# ADC.net
KiCad netlist of a schematic drawn in Altium Designer
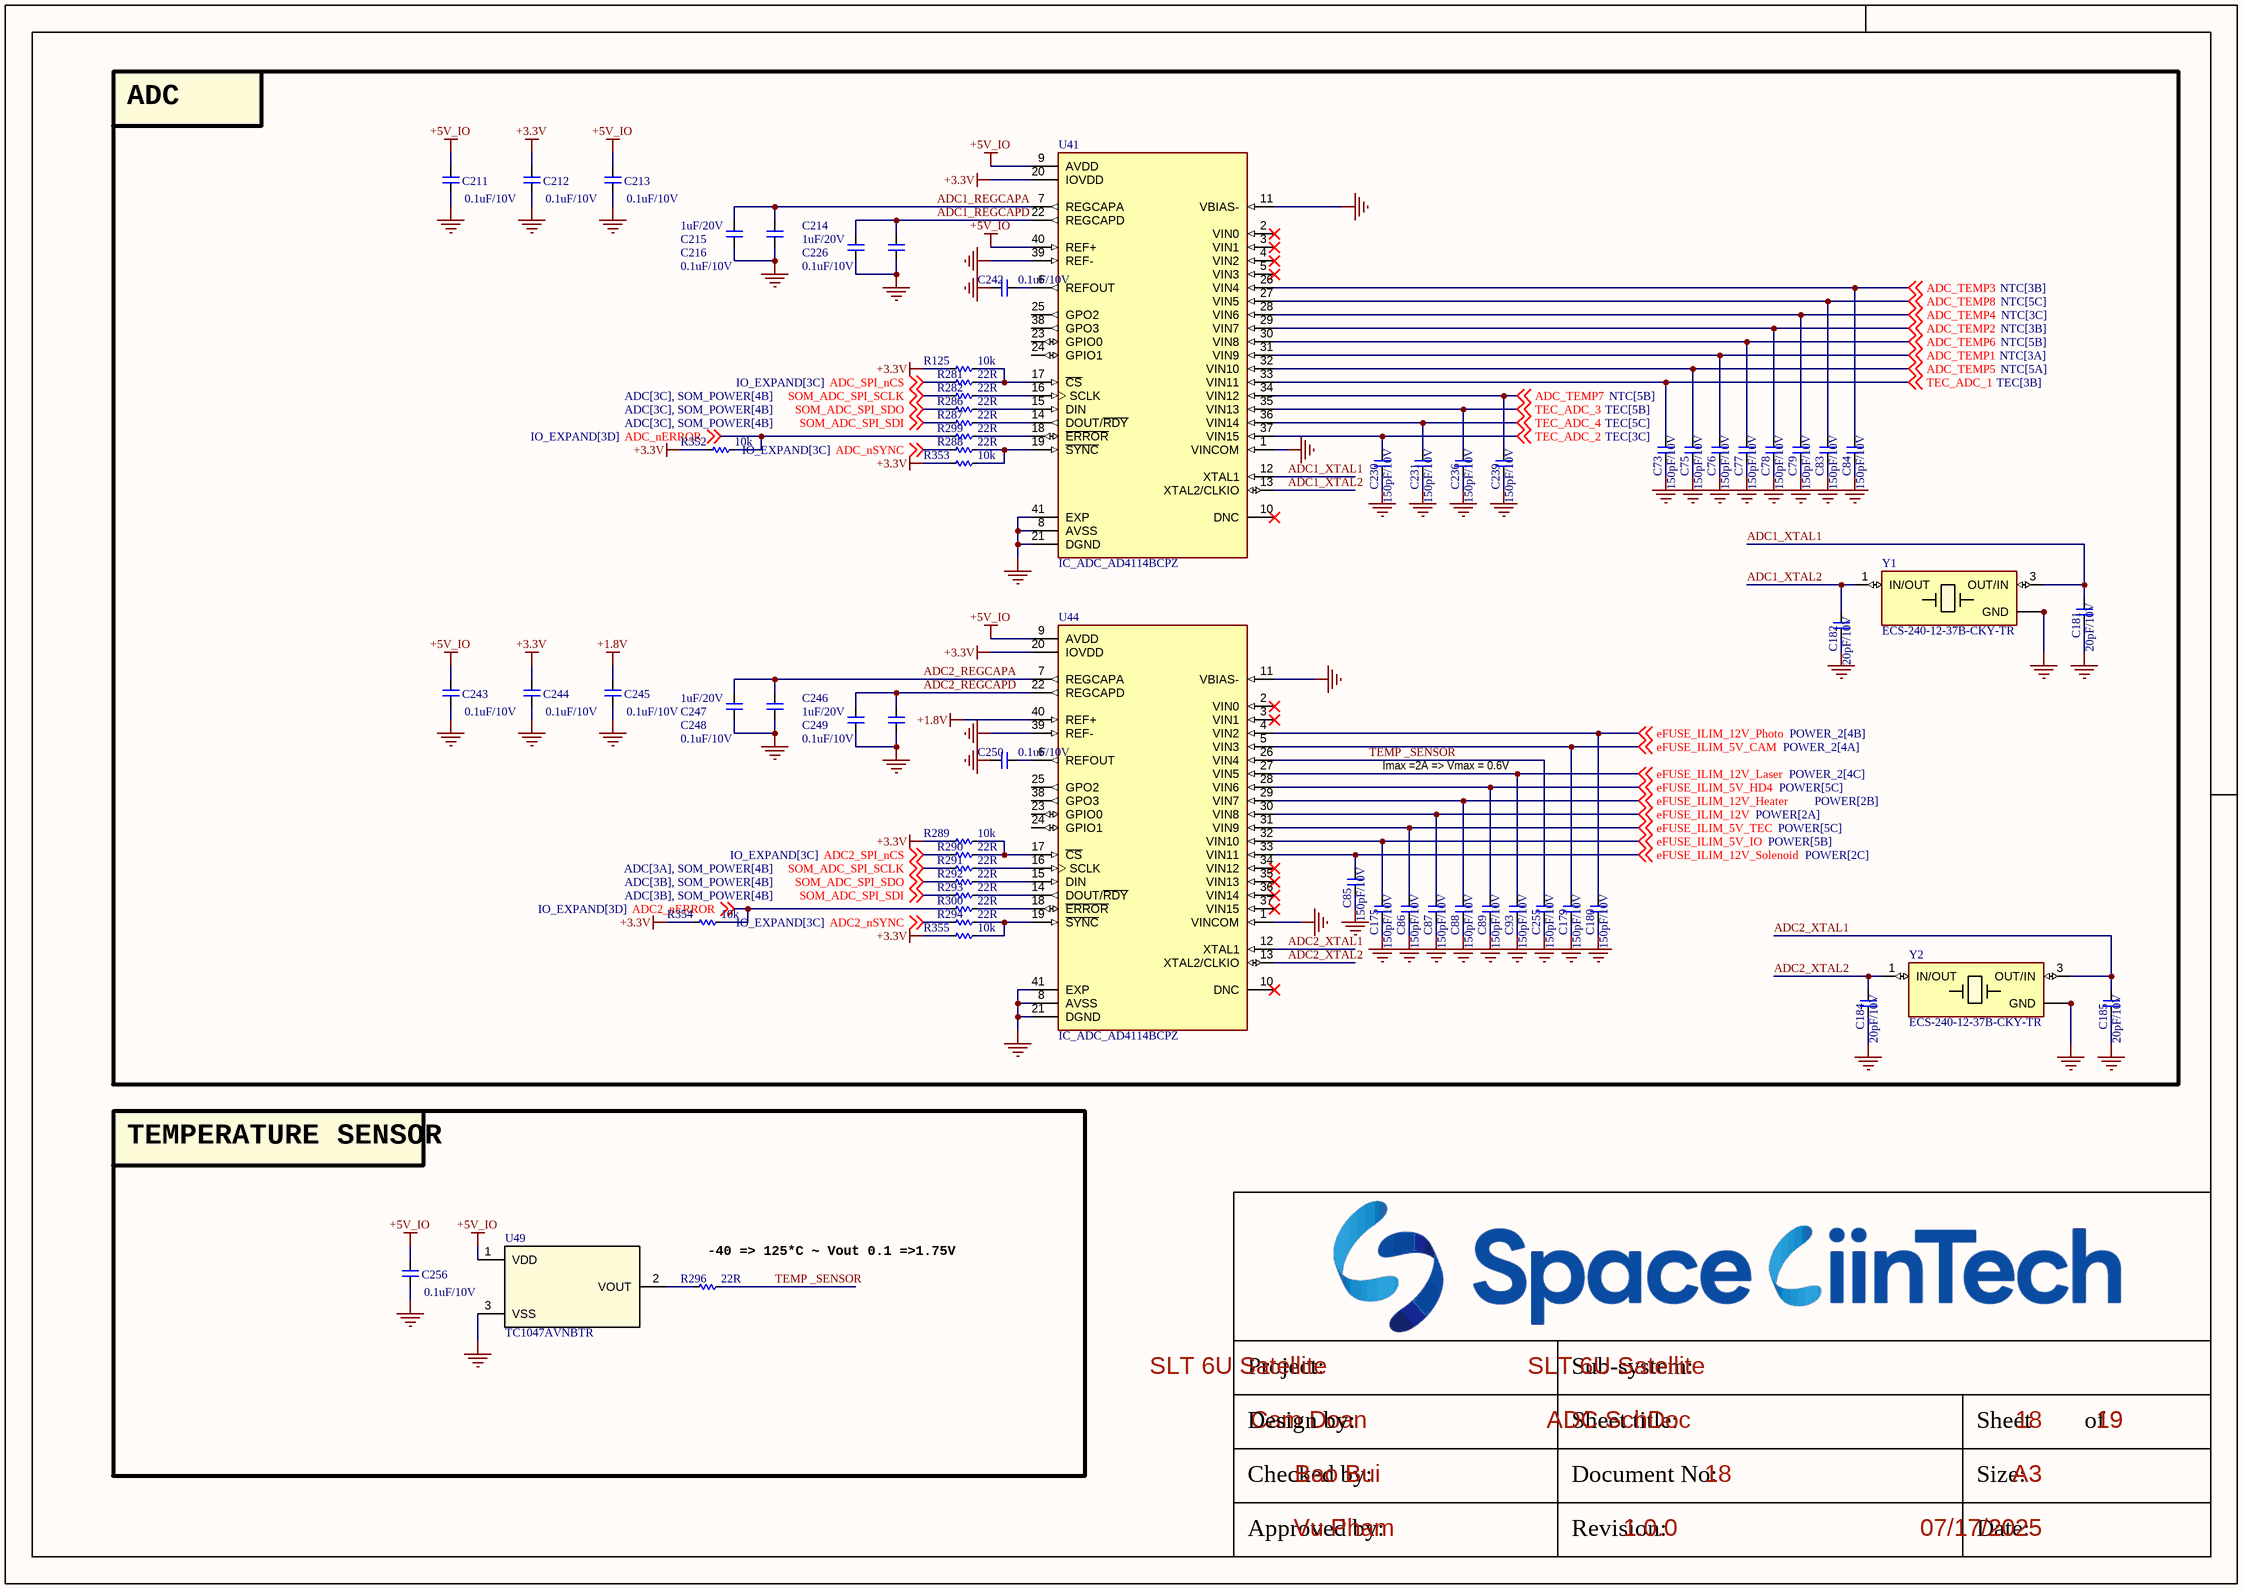
[diagram p0: ADC.SchDoc]

(export (version "E")
  (design (tool "Eeschema 10.0.6"))
  (components
    (comp (ref "C73")
      (value "150pF/10V")
      (footprint "CAP_C_1005X60")
      (description "CAP CHIP")
      (libsource (lib "LABLIB") (part "_CAP_C_2"))
    )
    (comp (ref "C75")
      (value "150pF/10V")
      (footprint "CAP_C_1005X60")
      (description "CAP CHIP")
      (libsource (lib "LABLIB") (part "_CAP_C_2"))
    )
    (comp (ref "C76")
      (value "150pF/10V")
      (footprint "CAP_C_1005X60")
      (description "CAP CHIP")
      (libsource (lib "LABLIB") (part "_CAP_C_2"))
    )
    (comp (ref "C77")
      (value "150pF/10V")
      (footprint "CAP_C_1005X60")
      (description "CAP CHIP")
      (libsource (lib "LABLIB") (part "_CAP_C_2"))
    )
    (comp (ref "C78")
      (value "150pF/10V")
      (footprint "CAP_C_1005X60")
      (description "CAP CHIP")
      (libsource (lib "LABLIB") (part "_CAP_C_2"))
    )
    (comp (ref "C79")
      (value "150pF/10V")
      (footprint "CAP_C_1005X60")
      (description "CAP CHIP")
      (libsource (lib "LABLIB") (part "_CAP_C_2"))
    )
    (comp (ref "C83")
      (value "150pF/10V")
      (footprint "CAP_C_1005X60")
      (description "CAP CHIP")
      (libsource (lib "LABLIB") (part "_CAP_C_2"))
    )
    (comp (ref "C84")
      (value "150pF/10V")
      (footprint "CAP_C_1005X60")
      (description "CAP CHIP")
      (libsource (lib "LABLIB") (part "_CAP_C_2"))
    )
    (comp (ref "C85")
      (value "150pF/10V")
      (footprint "CAP_C_1005X60")
      (description "CAP CHIP")
      (libsource (lib "LABLIB") (part "_CAP_C_2"))
    )
    (comp (ref "C86")
      (value "150pF/10V")
      (footprint "CAP_C_1005X60")
      (description "CAP CHIP")
      (libsource (lib "LABLIB") (part "_CAP_C_2"))
    )
    (comp (ref "C87")
      (value "150pF/10V")
      (footprint "CAP_C_1005X60")
      (description "CAP CHIP")
      (libsource (lib "LABLIB") (part "_CAP_C_2"))
    )
    (comp (ref "C88")
      (value "150pF/10V")
      (footprint "CAP_C_1005X60")
      (description "CAP CHIP")
      (libsource (lib "LABLIB") (part "_CAP_C_2"))
    )
    (comp (ref "C89")
      (value "150pF/10V")
      (footprint "CAP_C_1005X60")
      (description "CAP CHIP")
      (libsource (lib "LABLIB") (part "_CAP_C_2"))
    )
    (comp (ref "C93")
      (value "150pF/10V")
      (footprint "CAP_C_1005X60")
      (description "CAP CHIP")
      (libsource (lib "LABLIB") (part "_CAP_C_2"))
    )
    (comp (ref "C175")
      (value "150pF/10V")
      (footprint "CAP_C_1005X60")
      (description "CAP CHIP")
      (libsource (lib "LABLIB") (part "_CAP_C_2"))
    )
    (comp (ref "C179")
      (value "150pF/10V")
      (footprint "CAP_C_1005X60")
      (description "CAP CHIP")
      (libsource (lib "LABLIB") (part "_CAP_C_2"))
    )
    (comp (ref "C180")
      (value "150pF/10V")
      (footprint "CAP_C_1005X60")
      (description "CAP CHIP")
      (libsource (lib "LABLIB") (part "_CAP_C_2"))
    )
    (comp (ref "C181")
      (value "20pF/10V")
      (footprint "CAP_C_1005X60")
      (description "CAP CHIP")
      (libsource (lib "LABLIB") (part "_CAP_C_2"))
    )
    (comp (ref "C182")
      (value "20pF/10V")
      (footprint "CAP_C_1005X60")
      (description "CAP CHIP")
      (libsource (lib "LABLIB") (part "_CAP_C_2"))
    )
    (comp (ref "C184")
      (value "20pF/10V")
      (footprint "CAP_C_1005X60")
      (description "CAP CHIP")
      (libsource (lib "LABLIB") (part "_CAP_C_2"))
    )
    (comp (ref "C185")
      (value "20pF/10V")
      (footprint "CAP_C_1005X60")
      (description "CAP CHIP")
      (libsource (lib "LABLIB") (part "_CAP_C_2"))
    )
    (comp (ref "C211")
      (value "0.1uF/10V")
      (footprint "CAP_C_1005X60")
      (description "CAP CHIP")
      (libsource (lib "LABLIB") (part "_CAP_C_2"))
    )
    (comp (ref "C212")
      (value "0.1uF/10V")
      (footprint "CAP_C_1005X60")
      (description "CAP CHIP")
      (libsource (lib "LABLIB") (part "_CAP_C_2"))
    )
    (comp (ref "C213")
      (value "0.1uF/10V")
      (footprint "CAP_C_1005X60")
      (description "CAP CHIP")
      (libsource (lib "LABLIB") (part "_CAP_C_2"))
    )
    (comp (ref "C214")
      (value "1uF/20V")
      (footprint "CAP_C_1005X60")
      (description "CAP CHIP")
      (libsource (lib "LABLIB") (part "_CAP_C_2"))
    )
    (comp (ref "C215")
      (value "1uF/20V")
      (footprint "CAP_C_1005X60")
      (description "CAP CHIP")
      (libsource (lib "LABLIB") (part "_CAP_C_2"))
    )
    (comp (ref "C216")
      (value "0.1uF/10V")
      (footprint "CAP_C_1005X60")
      (description "CAP CHIP")
      (libsource (lib "LABLIB") (part "_CAP_C_2"))
    )
    (comp (ref "C226")
      (value "0.1uF/10V")
      (footprint "CAP_C_1005X60")
      (description "CAP CHIP")
      (libsource (lib "LABLIB") (part "_CAP_C_2"))
    )
    (comp (ref "C230")
      (value "150pF/10V")
      (footprint "CAP_C_1005X60")
      (description "CAP CHIP")
      (libsource (lib "LABLIB") (part "_CAP_C_2"))
    )
    (comp (ref "C231")
      (value "150pF/10V")
      (footprint "CAP_C_1005X60")
      (description "CAP CHIP")
      (libsource (lib "LABLIB") (part "_CAP_C_2"))
    )
    (comp (ref "C236")
      (value "150pF/10V")
      (footprint "CAP_C_1005X60")
      (description "CAP CHIP")
      (libsource (lib "LABLIB") (part "_CAP_C_2"))
    )
    (comp (ref "C239")
      (value "150pF/10V")
      (footprint "CAP_C_1005X60")
      (description "CAP CHIP")
      (libsource (lib "LABLIB") (part "_CAP_C_2"))
    )
    (comp (ref "C242")
      (value "0.1uF/10V")
      (footprint "CAP_C_1005X60")
      (description "CAP CHIP")
      (libsource (lib "LABLIB") (part "_CAP_C_2"))
    )
    (comp (ref "C243")
      (value "0.1uF/10V")
      (footprint "CAP_C_1005X60")
      (description "CAP CHIP")
      (libsource (lib "LABLIB") (part "_CAP_C_2"))
    )
    (comp (ref "C244")
      (value "0.1uF/10V")
      (footprint "CAP_C_1005X60")
      (description "CAP CHIP")
      (libsource (lib "LABLIB") (part "_CAP_C_2"))
    )
    (comp (ref "C245")
      (value "0.1uF/10V")
      (footprint "CAP_C_1005X60")
      (description "CAP CHIP")
      (libsource (lib "LABLIB") (part "_CAP_C_2"))
    )
    (comp (ref "C246")
      (value "1uF/20V")
      (footprint "CAP_C_1005X60")
      (description "CAP CHIP")
      (libsource (lib "LABLIB") (part "_CAP_C_2"))
    )
    (comp (ref "C247")
      (value "1uF/20V")
      (footprint "CAP_C_1005X60")
      (description "CAP CHIP")
      (libsource (lib "LABLIB") (part "_CAP_C_2"))
    )
    (comp (ref "C248")
      (value "0.1uF/10V")
      (footprint "CAP_C_1005X60")
      (description "CAP CHIP")
      (libsource (lib "LABLIB") (part "_CAP_C_2"))
    )
    (comp (ref "C249")
      (value "0.1uF/10V")
      (footprint "CAP_C_1005X60")
      (description "CAP CHIP")
      (libsource (lib "LABLIB") (part "_CAP_C_2"))
    )
    (comp (ref "C250")
      (value "0.1uF/10V")
      (footprint "CAP_C_1005X60")
      (description "CAP CHIP")
      (libsource (lib "LABLIB") (part "_CAP_C_2"))
    )
    (comp (ref "C255")
      (value "150pF/10V")
      (footprint "CAP_C_1005X60")
      (description "CAP CHIP")
      (libsource (lib "LABLIB") (part "_CAP_C_2"))
    )
    (comp (ref "C256")
      (value "0.1uF/10V")
      (footprint "CAP_C_1005X60")
      (description "CAP CHIP")
      (libsource (lib "LABLIB") (part "_CAP_C_2"))
    )
    (comp (ref "R125")
      (value "10k")
      (footprint "RES_C_1005X40")
      (description "RES")
      (libsource (lib "LABLIB") (part "_RES_B_2"))
    )
    (comp (ref "R281")
      (value "22R")
      (footprint "RES_C_1005X40")
      (description "RES")
      (libsource (lib "LABLIB") (part "_RES_B_2"))
    )
    (comp (ref "R282")
      (value "22R")
      (footprint "RES_C_1005X40")
      (description "RES")
      (libsource (lib "LABLIB") (part "_RES_B_2"))
    )
    (comp (ref "R286")
      (value "22R")
      (footprint "RES_C_1005X40")
      (description "RES")
      (libsource (lib "LABLIB") (part "_RES_B_2"))
    )
    (comp (ref "R287")
      (value "22R")
      (footprint "RES_C_1005X40")
      (description "RES")
      (libsource (lib "LABLIB") (part "_RES_B_2"))
    )
    (comp (ref "R288")
      (value "22R")
      (footprint "RES_C_1005X40")
      (description "RES")
      (libsource (lib "LABLIB") (part "_RES_B_2"))
    )
    (comp (ref "R289")
      (value "10k")
      (footprint "RES_C_1005X40")
      (description "RES")
      (libsource (lib "LABLIB") (part "_RES_B_2"))
    )
    (comp (ref "R290")
      (value "22R")
      (footprint "RES_C_1005X40")
      (description "RES")
      (libsource (lib "LABLIB") (part "_RES_B_2"))
    )
    (comp (ref "R291")
      (value "22R")
      (footprint "RES_C_1005X40")
      (description "RES")
      (libsource (lib "LABLIB") (part "_RES_B_2"))
    )
    (comp (ref "R292")
      (value "22R")
      (footprint "RES_C_1005X40")
      (description "RES")
      (libsource (lib "LABLIB") (part "_RES_B_2"))
    )
    (comp (ref "R293")
      (value "22R")
      (footprint "RES_C_1005X40")
      (description "RES")
      (libsource (lib "LABLIB") (part "_RES_B_2"))
    )
    (comp (ref "R294")
      (value "22R")
      (footprint "RES_C_1005X40")
      (description "RES")
      (libsource (lib "LABLIB") (part "_RES_B_2"))
    )
    (comp (ref "R296")
      (value "22R")
      (footprint "RES_C_1005X40")
      (description "RES")
      (libsource (lib "LABLIB") (part "_RES_B_2"))
    )
    (comp (ref "R299")
      (value "22R")
      (footprint "RES_C_1005X40")
      (description "RES")
      (libsource (lib "LABLIB") (part "_RES_B_2"))
    )
    (comp (ref "R300")
      (value "22R")
      (footprint "RES_C_1005X40")
      (description "RES")
      (libsource (lib "LABLIB") (part "_RES_B_2"))
    )
    (comp (ref "R352")
      (value "10k")
      (footprint "RES_C_1005X40")
      (description "RES")
      (libsource (lib "LABLIB") (part "_RES_B_2"))
    )
    (comp (ref "R353")
      (value "10k")
      (footprint "RES_C_1005X40")
      (description "RES")
      (libsource (lib "LABLIB") (part "_RES_B_2"))
    )
    (comp (ref "R354")
      (value "10k")
      (footprint "RES_C_1005X40")
      (description "RES")
      (libsource (lib "LABLIB") (part "_RES_B_2"))
    )
    (comp (ref "R355")
      (value "10k")
      (footprint "RES_C_1005X40")
      (description "RES")
      (libsource (lib "LABLIB") (part "_RES_B_2"))
    )
    (comp (ref "U41")
      (value "IC_ADC_AD4114BCPZ")
      (footprint "QFN50P600X600X100-41N")
      (description "Single Supply, Multichannel, 31.25 kSPS, 24-Bit, Sigma-Delta ADC with Â±10 V Inputs")
      (fields (field (name "MP") "AD4114BCPZ") (field (name "MF") "Analog Devices"))
      (libsource (lib "LABLIB") (part "IC_ADC_AD4114BCPZ"))
    )
    (comp (ref "U44")
      (value "IC_ADC_AD4114BCPZ")
      (footprint "QFN50P600X600X100-41N")
      (description "Single Supply, Multichannel, 31.25 kSPS, 24-Bit, Sigma-Delta ADC with Â±10 V Inputs")
      (fields (field (name "MP") "AD4114BCPZ") (field (name "MF") "Analog Devices"))
      (libsource (lib "LABLIB") (part "IC_ADC_AD4114BCPZ"))
    )
    (comp (ref "U49")
      (value "TC1047AVNBTR")
      (footprint "SOT95P240X120-3N")
      (description "Temperature Sensor Analog, Local -40°C ~ 125°C 10mV/°C SOT-23-3")
      (libsource (lib "LABLIB") (part "IC_SENSOR_TC1047AVNBTR"))
    )
    (comp (ref "Y1")
      (value "ECS-240-12-37B-CKY-TR")
      (footprint "XTAL_ECS-240-12-37B-CKY-TR")
      (libsource (lib "ECS-240-12-37B-CKY-TR") (part "ECS-240-12-37B-CKY-TR"))
    )
    (comp (ref "Y2")
      (value "ECS-240-12-37B-CKY-TR")
      (footprint "XTAL_ECS-240-12-37B-CKY-TR")
      (libsource (lib "ECS-240-12-37B-CKY-TR") (part "ECS-240-12-37B-CKY-TR"))
    )
  )
  (nets
    (net (code "1") (name "+1.8V") (class "Default")
      (node (ref "C245") (pin "2") (pinfunction "2_2") (pintype "passive"))
      (node (ref "U44") (pin "40") (pinfunction "REF+_40") (pintype "input"))
    )
    (net (code "2") (name "+3.3V") (class "Default")
      (node (ref "C212") (pin "2") (pinfunction "2_2") (pintype "passive"))
      (node (ref "C244") (pin "2") (pinfunction "2_2") (pintype "passive"))
      (node (ref "R125") (pin "2") (pinfunction "2_2") (pintype "passive"))
      (node (ref "R289") (pin "2") (pinfunction "2_2") (pintype "passive"))
      (node (ref "R352") (pin "2") (pinfunction "2_2") (pintype "passive"))
      (node (ref "R353") (pin "2") (pinfunction "2_2") (pintype "passive"))
      (node (ref "R354") (pin "2") (pinfunction "2_2") (pintype "passive"))
      (node (ref "R355") (pin "2") (pinfunction "2_2") (pintype "passive"))
      (node (ref "U41") (pin "20") (pinfunction "IOVDD_20") (pintype "power_in"))
      (node (ref "U44") (pin "20") (pinfunction "IOVDD_20") (pintype "power_in"))
    )
    (net (code "3") (name "+5V_IO") (class "Default")
      (node (ref "C211") (pin "2") (pinfunction "2_2") (pintype "passive"))
      (node (ref "C213") (pin "2") (pinfunction "2_2") (pintype "passive"))
      (node (ref "C243") (pin "2") (pinfunction "2_2") (pintype "passive"))
      (node (ref "C256") (pin "2") (pinfunction "2_2") (pintype "passive"))
      (node (ref "U41") (pin "40") (pinfunction "REF+_40") (pintype "input"))
      (node (ref "U41") (pin "9") (pinfunction "AVDD_9") (pintype "power_in"))
      (node (ref "U44") (pin "9") (pinfunction "AVDD_9") (pintype "power_in"))
      (node (ref "U49") (pin "1") (pinfunction "VDD_1") (pintype "passive"))
    )
    (net (code "4") (name "/ADC1_REGCAPA") (class "Default")
      (node (ref "C215") (pin "2") (pinfunction "2_2") (pintype "passive"))
      (node (ref "C216") (pin "2") (pinfunction "2_2") (pintype "passive"))
      (node (ref "U41") (pin "7") (pinfunction "REGCAPA_7") (pintype "output"))
    )
    (net (code "5") (name "/ADC1_REGCAPD") (class "Default")
      (node (ref "C214") (pin "2") (pinfunction "2_2") (pintype "passive"))
      (node (ref "C226") (pin "2") (pinfunction "2_2") (pintype "passive"))
      (node (ref "U41") (pin "22") (pinfunction "REGCAPD_22") (pintype "output"))
    )
    (net (code "6") (name "/ADC1_XTAL1") (class "Default")
      (node (ref "C181") (pin "2") (pinfunction "2_2") (pintype "passive"))
      (node (ref "U41") (pin "12") (pinfunction "XTAL1_12") (pintype "input"))
      (node (ref "Y1") (pin "3") (pinfunction "OUT/IN_3") (pintype "bidirectional"))
    )
    (net (code "7") (name "/ADC1_XTAL2") (class "Default")
      (node (ref "C182") (pin "2") (pinfunction "2_2") (pintype "passive"))
      (node (ref "U41") (pin "13") (pinfunction "XTAL2/CLKIO_13") (pintype "bidirectional"))
      (node (ref "Y1") (pin "1") (pinfunction "IN/OUT_1") (pintype "bidirectional"))
    )
    (net (code "8") (name "/ADC2_REGCAPA") (class "Default")
      (node (ref "C247") (pin "2") (pinfunction "2_2") (pintype "passive"))
      (node (ref "C248") (pin "2") (pinfunction "2_2") (pintype "passive"))
      (node (ref "U44") (pin "7") (pinfunction "REGCAPA_7") (pintype "output"))
    )
    (net (code "9") (name "/ADC2_REGCAPD") (class "Default")
      (node (ref "C246") (pin "2") (pinfunction "2_2") (pintype "passive"))
      (node (ref "C249") (pin "2") (pinfunction "2_2") (pintype "passive"))
      (node (ref "U44") (pin "22") (pinfunction "REGCAPD_22") (pintype "output"))
    )
    (net (code "10") (name "/ADC2_XTAL1") (class "Default")
      (node (ref "C185") (pin "2") (pinfunction "2_2") (pintype "passive"))
      (node (ref "U44") (pin "12") (pinfunction "XTAL1_12") (pintype "input"))
      (node (ref "Y2") (pin "3") (pinfunction "OUT/IN_3") (pintype "bidirectional"))
    )
    (net (code "11") (name "/ADC2_XTAL2") (class "Default")
      (node (ref "C184") (pin "2") (pinfunction "2_2") (pintype "passive"))
      (node (ref "U44") (pin "13") (pinfunction "XTAL2/CLKIO_13") (pintype "bidirectional"))
      (node (ref "Y2") (pin "1") (pinfunction "IN/OUT_1") (pintype "bidirectional"))
    )
    (net (code "12") (name "/TEMP _SENSOR") (class "Default")
      (node (ref "C255") (pin "2") (pinfunction "2_2") (pintype "passive"))
      (node (ref "R296") (pin "2") (pinfunction "2_2") (pintype "passive"))
      (node (ref "U44") (pin "26") (pinfunction "VIN4_26") (pintype "input"))
    )
    (net (code "13") (name "ADC2_SPI_nCS") (class "Default")
      (node (ref "R290") (pin "1") (pinfunction "1_1") (pintype "passive"))
    )
    (net (code "14") (name "ADC2_nERROR") (class "Default")
      (node (ref "R300") (pin "1") (pinfunction "1_1") (pintype "passive"))
      (node (ref "R354") (pin "1") (pinfunction "1_1") (pintype "passive"))
    )
    (net (code "15") (name "ADC2_nSYNC") (class "Default")
      (node (ref "R294") (pin "1") (pinfunction "1_1") (pintype "passive"))
    )
    (net (code "16") (name "ADC_SPI_nCS") (class "Default")
      (node (ref "R281") (pin "1") (pinfunction "1_1") (pintype "passive"))
    )
    (net (code "17") (name "ADC_TEMP1") (class "Default")
      (node (ref "C76") (pin "2") (pinfunction "2_2") (pintype "passive"))
      (node (ref "U41") (pin "31") (pinfunction "VIN9_31") (pintype "input"))
    )
    (net (code "18") (name "ADC_TEMP2") (class "Default")
      (node (ref "C78") (pin "2") (pinfunction "2_2") (pintype "passive"))
      (node (ref "U41") (pin "29") (pinfunction "VIN7_29") (pintype "input"))
    )
    (net (code "19") (name "ADC_TEMP3") (class "Default")
      (node (ref "C84") (pin "2") (pinfunction "2_2") (pintype "passive"))
      (node (ref "U41") (pin "26") (pinfunction "VIN4_26") (pintype "input"))
    )
    (net (code "20") (name "ADC_TEMP4") (class "Default")
      (node (ref "C79") (pin "2") (pinfunction "2_2") (pintype "passive"))
      (node (ref "U41") (pin "28") (pinfunction "VIN6_28") (pintype "input"))
    )
    (net (code "21") (name "ADC_TEMP5") (class "Default")
      (node (ref "C75") (pin "2") (pinfunction "2_2") (pintype "passive"))
      (node (ref "U41") (pin "32") (pinfunction "VIN10_32") (pintype "input"))
    )
    (net (code "22") (name "ADC_TEMP6") (class "Default")
      (node (ref "C77") (pin "2") (pinfunction "2_2") (pintype "passive"))
      (node (ref "U41") (pin "30") (pinfunction "VIN8_30") (pintype "input"))
    )
    (net (code "23") (name "ADC_TEMP7") (class "Default")
      (node (ref "C239") (pin "2") (pinfunction "2_2") (pintype "passive"))
      (node (ref "U41") (pin "34") (pinfunction "VIN12_34") (pintype "input"))
    )
    (net (code "24") (name "ADC_TEMP8") (class "Default")
      (node (ref "C83") (pin "2") (pinfunction "2_2") (pintype "passive"))
      (node (ref "U41") (pin "27") (pinfunction "VIN5_27") (pintype "input"))
    )
    (net (code "25") (name "ADC_nERROR") (class "Default")
      (node (ref "R299") (pin "1") (pinfunction "1_1") (pintype "passive"))
      (node (ref "R352") (pin "1") (pinfunction "1_1") (pintype "passive"))
    )
    (net (code "26") (name "ADC_nSYNC") (class "Default")
      (node (ref "R288") (pin "1") (pinfunction "1_1") (pintype "passive"))
    )
    (net (code "27") (name "GND") (class "Default")
      (node (ref "C175") (pin "1") (pinfunction "1_1") (pintype "passive"))
      (node (ref "C179") (pin "1") (pinfunction "1_1") (pintype "passive"))
      (node (ref "C180") (pin "1") (pinfunction "1_1") (pintype "passive"))
      (node (ref "C181") (pin "1") (pinfunction "1_1") (pintype "passive"))
      (node (ref "C182") (pin "1") (pinfunction "1_1") (pintype "passive"))
      (node (ref "C184") (pin "1") (pinfunction "1_1") (pintype "passive"))
      (node (ref "C185") (pin "1") (pinfunction "1_1") (pintype "passive"))
      (node (ref "C211") (pin "1") (pinfunction "1_1") (pintype "passive"))
      (node (ref "C212") (pin "1") (pinfunction "1_1") (pintype "passive"))
      (node (ref "C213") (pin "1") (pinfunction "1_1") (pintype "passive"))
      (node (ref "C214") (pin "1") (pinfunction "1_1") (pintype "passive"))
      (node (ref "C215") (pin "1") (pinfunction "1_1") (pintype "passive"))
      (node (ref "C216") (pin "1") (pinfunction "1_1") (pintype "passive"))
      (node (ref "C226") (pin "1") (pinfunction "1_1") (pintype "passive"))
      (node (ref "C230") (pin "1") (pinfunction "1_1") (pintype "passive"))
      (node (ref "C231") (pin "1") (pinfunction "1_1") (pintype "passive"))
      (node (ref "C236") (pin "1") (pinfunction "1_1") (pintype "passive"))
      (node (ref "C239") (pin "1") (pinfunction "1_1") (pintype "passive"))
      (node (ref "C242") (pin "1") (pinfunction "1_1") (pintype "passive"))
      (node (ref "C243") (pin "1") (pinfunction "1_1") (pintype "passive"))
      (node (ref "C244") (pin "1") (pinfunction "1_1") (pintype "passive"))
      (node (ref "C245") (pin "1") (pinfunction "1_1") (pintype "passive"))
      (node (ref "C246") (pin "1") (pinfunction "1_1") (pintype "passive"))
      (node (ref "C247") (pin "1") (pinfunction "1_1") (pintype "passive"))
      (node (ref "C248") (pin "1") (pinfunction "1_1") (pintype "passive"))
      (node (ref "C249") (pin "1") (pinfunction "1_1") (pintype "passive"))
      (node (ref "C250") (pin "1") (pinfunction "1_1") (pintype "passive"))
      (node (ref "C255") (pin "1") (pinfunction "1_1") (pintype "passive"))
      (node (ref "C256") (pin "1") (pinfunction "1_1") (pintype "passive"))
      (node (ref "C73") (pin "1") (pinfunction "1_1") (pintype "passive"))
      (node (ref "C75") (pin "1") (pinfunction "1_1") (pintype "passive"))
      (node (ref "C76") (pin "1") (pinfunction "1_1") (pintype "passive"))
      (node (ref "C77") (pin "1") (pinfunction "1_1") (pintype "passive"))
      (node (ref "C78") (pin "1") (pinfunction "1_1") (pintype "passive"))
      (node (ref "C79") (pin "1") (pinfunction "1_1") (pintype "passive"))
      (node (ref "C83") (pin "1") (pinfunction "1_1") (pintype "passive"))
      (node (ref "C84") (pin "1") (pinfunction "1_1") (pintype "passive"))
      (node (ref "C85") (pin "1") (pinfunction "1_1") (pintype "passive"))
      (node (ref "C86") (pin "1") (pinfunction "1_1") (pintype "passive"))
      (node (ref "C87") (pin "1") (pinfunction "1_1") (pintype "passive"))
      (node (ref "C88") (pin "1") (pinfunction "1_1") (pintype "passive"))
      (node (ref "C89") (pin "1") (pinfunction "1_1") (pintype "passive"))
      (node (ref "C93") (pin "1") (pinfunction "1_1") (pintype "passive"))
      (node (ref "U41") (pin "1") (pinfunction "VINCOM_1") (pintype "input"))
      (node (ref "U41") (pin "11") (pinfunction "VBIAS-_11") (pintype "input"))
      (node (ref "U41") (pin "21") (pinfunction "DGND_21") (pintype "power_in"))
      (node (ref "U41") (pin "39") (pinfunction "REF-_39") (pintype "input"))
      (node (ref "U41") (pin "41") (pinfunction "EXP_41") (pintype "power_in"))
      (node (ref "U41") (pin "8") (pinfunction "AVSS_8") (pintype "power_in"))
      (node (ref "U44") (pin "1") (pinfunction "VINCOM_1") (pintype "input"))
      (node (ref "U44") (pin "11") (pinfunction "VBIAS-_11") (pintype "input"))
      (node (ref "U44") (pin "21") (pinfunction "DGND_21") (pintype "power_in"))
      (node (ref "U44") (pin "39") (pinfunction "REF-_39") (pintype "input"))
      (node (ref "U44") (pin "41") (pinfunction "EXP_41") (pintype "power_in"))
      (node (ref "U44") (pin "8") (pinfunction "AVSS_8") (pintype "power_in"))
      (node (ref "U49") (pin "3") (pinfunction "VSS_3") (pintype "passive"))
      (node (ref "Y1") (pin "2") (pinfunction "GND_2") (pintype "power_in"))
      (node (ref "Y1") (pin "4") (pinfunction "GND_4") (pintype "power_in"))
      (node (ref "Y2") (pin "2") (pinfunction "GND_2") (pintype "power_in"))
      (node (ref "Y2") (pin "4") (pinfunction "GND_4") (pintype "power_in"))
    )
    (net (code "28") (name "Net-(U41-DIN)") (class "Default")
      (node (ref "R286") (pin "2") (pinfunction "2_2") (pintype "passive"))
      (node (ref "U41") (pin "15") (pinfunction "DIN_15") (pintype "input"))
    )
    (net (code "29") (name "Net-(U41-DOUT{slash}~{RDY})") (class "Default")
      (node (ref "R287") (pin "2") (pinfunction "2_2") (pintype "passive"))
      (node (ref "U41") (pin "14") (pinfunction "DOUT/~{RDY}_14") (pintype "output"))
    )
    (net (code "30") (name "Net-(U41-REFOUT)") (class "Default")
      (node (ref "C242") (pin "2") (pinfunction "2_2") (pintype "passive"))
      (node (ref "U41") (pin "6") (pinfunction "REFOUT_6") (pintype "output"))
    )
    (net (code "31") (name "Net-(U41-SCLK)") (class "Default")
      (node (ref "R282") (pin "2") (pinfunction "2_2") (pintype "passive"))
      (node (ref "U41") (pin "16") (pinfunction "SCLK_16") (pintype "input"))
    )
    (net (code "32") (name "Net-(U41-~{CS})") (class "Default")
      (node (ref "R125") (pin "1") (pinfunction "1_1") (pintype "passive"))
      (node (ref "R281") (pin "2") (pinfunction "2_2") (pintype "passive"))
      (node (ref "U41") (pin "17") (pinfunction "~{CS}_17") (pintype "input"))
    )
    (net (code "33") (name "Net-(U41-~{ERROR})") (class "Default")
      (node (ref "R299") (pin "2") (pinfunction "2_2") (pintype "passive"))
      (node (ref "U41") (pin "18") (pinfunction "~{ERROR}_18") (pintype "bidirectional"))
    )
    (net (code "34") (name "Net-(U41-~{SYNC})") (class "Default")
      (node (ref "R288") (pin "2") (pinfunction "2_2") (pintype "passive"))
      (node (ref "R353") (pin "1") (pinfunction "1_1") (pintype "passive"))
      (node (ref "U41") (pin "19") (pinfunction "~{SYNC}_19") (pintype "input"))
    )
    (net (code "35") (name "Net-(U44-DIN)") (class "Default")
      (node (ref "R292") (pin "2") (pinfunction "2_2") (pintype "passive"))
      (node (ref "U44") (pin "15") (pinfunction "DIN_15") (pintype "input"))
    )
    (net (code "36") (name "Net-(U44-DOUT{slash}~{RDY})") (class "Default")
      (node (ref "R293") (pin "2") (pinfunction "2_2") (pintype "passive"))
      (node (ref "U44") (pin "14") (pinfunction "DOUT/~{RDY}_14") (pintype "output"))
    )
    (net (code "37") (name "Net-(U44-REFOUT)") (class "Default")
      (node (ref "C250") (pin "2") (pinfunction "2_2") (pintype "passive"))
      (node (ref "U44") (pin "6") (pinfunction "REFOUT_6") (pintype "output"))
    )
    (net (code "38") (name "Net-(U44-SCLK)") (class "Default")
      (node (ref "R291") (pin "2") (pinfunction "2_2") (pintype "passive"))
      (node (ref "U44") (pin "16") (pinfunction "SCLK_16") (pintype "input"))
    )
    (net (code "39") (name "Net-(U44-~{CS})") (class "Default")
      (node (ref "R289") (pin "1") (pinfunction "1_1") (pintype "passive"))
      (node (ref "R290") (pin "2") (pinfunction "2_2") (pintype "passive"))
      (node (ref "U44") (pin "17") (pinfunction "~{CS}_17") (pintype "input"))
    )
    (net (code "40") (name "Net-(U44-~{ERROR})") (class "Default")
      (node (ref "R300") (pin "2") (pinfunction "2_2") (pintype "passive"))
      (node (ref "U44") (pin "18") (pinfunction "~{ERROR}_18") (pintype "bidirectional"))
    )
    (net (code "41") (name "Net-(U44-~{SYNC})") (class "Default")
      (node (ref "R294") (pin "2") (pinfunction "2_2") (pintype "passive"))
      (node (ref "R355") (pin "1") (pinfunction "1_1") (pintype "passive"))
      (node (ref "U44") (pin "19") (pinfunction "~{SYNC}_19") (pintype "input"))
    )
    (net (code "42") (name "Net-(U49-VOUT)") (class "Default")
      (node (ref "R296") (pin "1") (pinfunction "1_1") (pintype "passive"))
      (node (ref "U49") (pin "2") (pinfunction "VOUT_2") (pintype "passive"))
    )
    (net (code "43") (name "SOM_ADC_SPI_SCLK") (class "Default")
      (node (ref "R282") (pin "1") (pinfunction "1_1") (pintype "passive"))
      (node (ref "R291") (pin "1") (pinfunction "1_1") (pintype "passive"))
    )
    (net (code "44") (name "SOM_ADC_SPI_SDI") (class "Default")
      (node (ref "R287") (pin "1") (pinfunction "1_1") (pintype "passive"))
      (node (ref "R293") (pin "1") (pinfunction "1_1") (pintype "passive"))
    )
    (net (code "45") (name "SOM_ADC_SPI_SDO") (class "Default")
      (node (ref "R286") (pin "1") (pinfunction "1_1") (pintype "passive"))
      (node (ref "R292") (pin "1") (pinfunction "1_1") (pintype "passive"))
    )
    (net (code "46") (name "TEC_ADC_1") (class "Default")
      (node (ref "C73") (pin "2") (pinfunction "2_2") (pintype "passive"))
      (node (ref "U41") (pin "33") (pinfunction "VIN11_33") (pintype "input"))
    )
    (net (code "47") (name "TEC_ADC_2") (class "Default")
      (node (ref "C230") (pin "2") (pinfunction "2_2") (pintype "passive"))
      (node (ref "U41") (pin "37") (pinfunction "VIN15_37") (pintype "input"))
    )
    (net (code "48") (name "TEC_ADC_3") (class "Default")
      (node (ref "C236") (pin "2") (pinfunction "2_2") (pintype "passive"))
      (node (ref "U41") (pin "35") (pinfunction "VIN13_35") (pintype "input"))
    )
    (net (code "49") (name "TEC_ADC_4") (class "Default")
      (node (ref "C231") (pin "2") (pinfunction "2_2") (pintype "passive"))
      (node (ref "U41") (pin "36") (pinfunction "VIN14_36") (pintype "input"))
    )
    (net (code "50") (name "eFUSE_ILIM_5V_CAM") (class "Default")
      (node (ref "C179") (pin "2") (pinfunction "2_2") (pintype "passive"))
      (node (ref "U44") (pin "5") (pinfunction "VIN3_5") (pintype "input"))
    )
    (net (code "51") (name "eFUSE_ILIM_5V_HD4") (class "Default")
      (node (ref "C89") (pin "2") (pinfunction "2_2") (pintype "passive"))
      (node (ref "U44") (pin "28") (pinfunction "VIN6_28") (pintype "input"))
    )
    (net (code "52") (name "eFUSE_ILIM_5V_IO") (class "Default")
      (node (ref "C175") (pin "2") (pinfunction "2_2") (pintype "passive"))
      (node (ref "U44") (pin "32") (pinfunction "VIN10_32") (pintype "input"))
    )
    (net (code "53") (name "eFUSE_ILIM_5V_TEC") (class "Default")
      (node (ref "C86") (pin "2") (pinfunction "2_2") (pintype "passive"))
      (node (ref "U44") (pin "31") (pinfunction "VIN9_31") (pintype "input"))
    )
    (net (code "54") (name "eFUSE_ILIM_12V") (class "Default")
      (node (ref "C87") (pin "2") (pinfunction "2_2") (pintype "passive"))
      (node (ref "U44") (pin "30") (pinfunction "VIN8_30") (pintype "input"))
    )
    (net (code "55") (name "eFUSE_ILIM_12V_Heater") (class "Default")
      (node (ref "C88") (pin "2") (pinfunction "2_2") (pintype "passive"))
      (node (ref "U44") (pin "29") (pinfunction "VIN7_29") (pintype "input"))
    )
    (net (code "56") (name "eFUSE_ILIM_12V_Laser") (class "Default")
      (node (ref "C93") (pin "2") (pinfunction "2_2") (pintype "passive"))
      (node (ref "U44") (pin "27") (pinfunction "VIN5_27") (pintype "input"))
    )
    (net (code "57") (name "eFUSE_ILIM_12V_Photo") (class "Default")
      (node (ref "C180") (pin "2") (pinfunction "2_2") (pintype "passive"))
      (node (ref "U44") (pin "4") (pinfunction "VIN2_4") (pintype "input"))
    )
    (net (code "58") (name "eFUSE_ILIM_12V_Solenoid") (class "Default")
      (node (ref "C85") (pin "2") (pinfunction "2_2") (pintype "passive"))
      (node (ref "U44") (pin "33") (pinfunction "VIN11_33") (pintype "input"))
    )
    (net (code "59") (name "unconnected-(U41-DNC-Pad10)") (class "Default")
      (node (ref "U41") (pin "10") (pinfunction "DNC_10") (pintype "passive+no_connect"))
    )
    (net (code "60") (name "unconnected-(U41-GPIO0-Pad23)") (class "Default")
      (node (ref "U41") (pin "23") (pinfunction "GPIO0_23") (pintype "bidirectional"))
    )
    (net (code "61") (name "unconnected-(U41-GPIO1-Pad24)") (class "Default")
      (node (ref "U41") (pin "24") (pinfunction "GPIO1_24") (pintype "bidirectional"))
    )
    (net (code "62") (name "unconnected-(U41-GPO2-Pad25)") (class "Default")
      (node (ref "U41") (pin "25") (pinfunction "GPO2_25") (pintype "output"))
    )
    (net (code "63") (name "unconnected-(U41-GPO3-Pad38)") (class "Default")
      (node (ref "U41") (pin "38") (pinfunction "GPO3_38") (pintype "output"))
    )
    (net (code "64") (name "unconnected-(U41-VIN0-Pad2)") (class "Default")
      (node (ref "U41") (pin "2") (pinfunction "VIN0_2") (pintype "input+no_connect"))
    )
    (net (code "65") (name "unconnected-(U41-VIN1-Pad3)") (class "Default")
      (node (ref "U41") (pin "3") (pinfunction "VIN1_3") (pintype "input+no_connect"))
    )
    (net (code "66") (name "unconnected-(U41-VIN2-Pad4)") (class "Default")
      (node (ref "U41") (pin "4") (pinfunction "VIN2_4") (pintype "input+no_connect"))
    )
    (net (code "67") (name "unconnected-(U41-VIN3-Pad5)") (class "Default")
      (node (ref "U41") (pin "5") (pinfunction "VIN3_5") (pintype "input+no_connect"))
    )
    (net (code "68") (name "unconnected-(U44-DNC-Pad10)") (class "Default")
      (node (ref "U44") (pin "10") (pinfunction "DNC_10") (pintype "passive+no_connect"))
    )
    (net (code "69") (name "unconnected-(U44-GPIO0-Pad23)") (class "Default")
      (node (ref "U44") (pin "23") (pinfunction "GPIO0_23") (pintype "bidirectional"))
    )
    (net (code "70") (name "unconnected-(U44-GPIO1-Pad24)") (class "Default")
      (node (ref "U44") (pin "24") (pinfunction "GPIO1_24") (pintype "bidirectional"))
    )
    (net (code "71") (name "unconnected-(U44-GPO2-Pad25)") (class "Default")
      (node (ref "U44") (pin "25") (pinfunction "GPO2_25") (pintype "output"))
    )
    (net (code "72") (name "unconnected-(U44-GPO3-Pad38)") (class "Default")
      (node (ref "U44") (pin "38") (pinfunction "GPO3_38") (pintype "output"))
    )
    (net (code "73") (name "unconnected-(U44-VIN0-Pad2)") (class "Default")
      (node (ref "U44") (pin "2") (pinfunction "VIN0_2") (pintype "input+no_connect"))
    )
    (net (code "74") (name "unconnected-(U44-VIN1-Pad3)") (class "Default")
      (node (ref "U44") (pin "3") (pinfunction "VIN1_3") (pintype "input+no_connect"))
    )
    (net (code "75") (name "unconnected-(U44-VIN12-Pad34)") (class "Default")
      (node (ref "U44") (pin "34") (pinfunction "VIN12_34") (pintype "input+no_connect"))
    )
    (net (code "76") (name "unconnected-(U44-VIN13-Pad35)") (class "Default")
      (node (ref "U44") (pin "35") (pinfunction "VIN13_35") (pintype "input+no_connect"))
    )
    (net (code "77") (name "unconnected-(U44-VIN14-Pad36)") (class "Default")
      (node (ref "U44") (pin "36") (pinfunction "VIN14_36") (pintype "input+no_connect"))
    )
    (net (code "78") (name "unconnected-(U44-VIN15-Pad37)") (class "Default")
      (node (ref "U44") (pin "37") (pinfunction "VIN15_37") (pintype "input+no_connect"))
    )
  )
)
